# PCB.net
KiCad netlist of a schematic drawn in Altium Designer
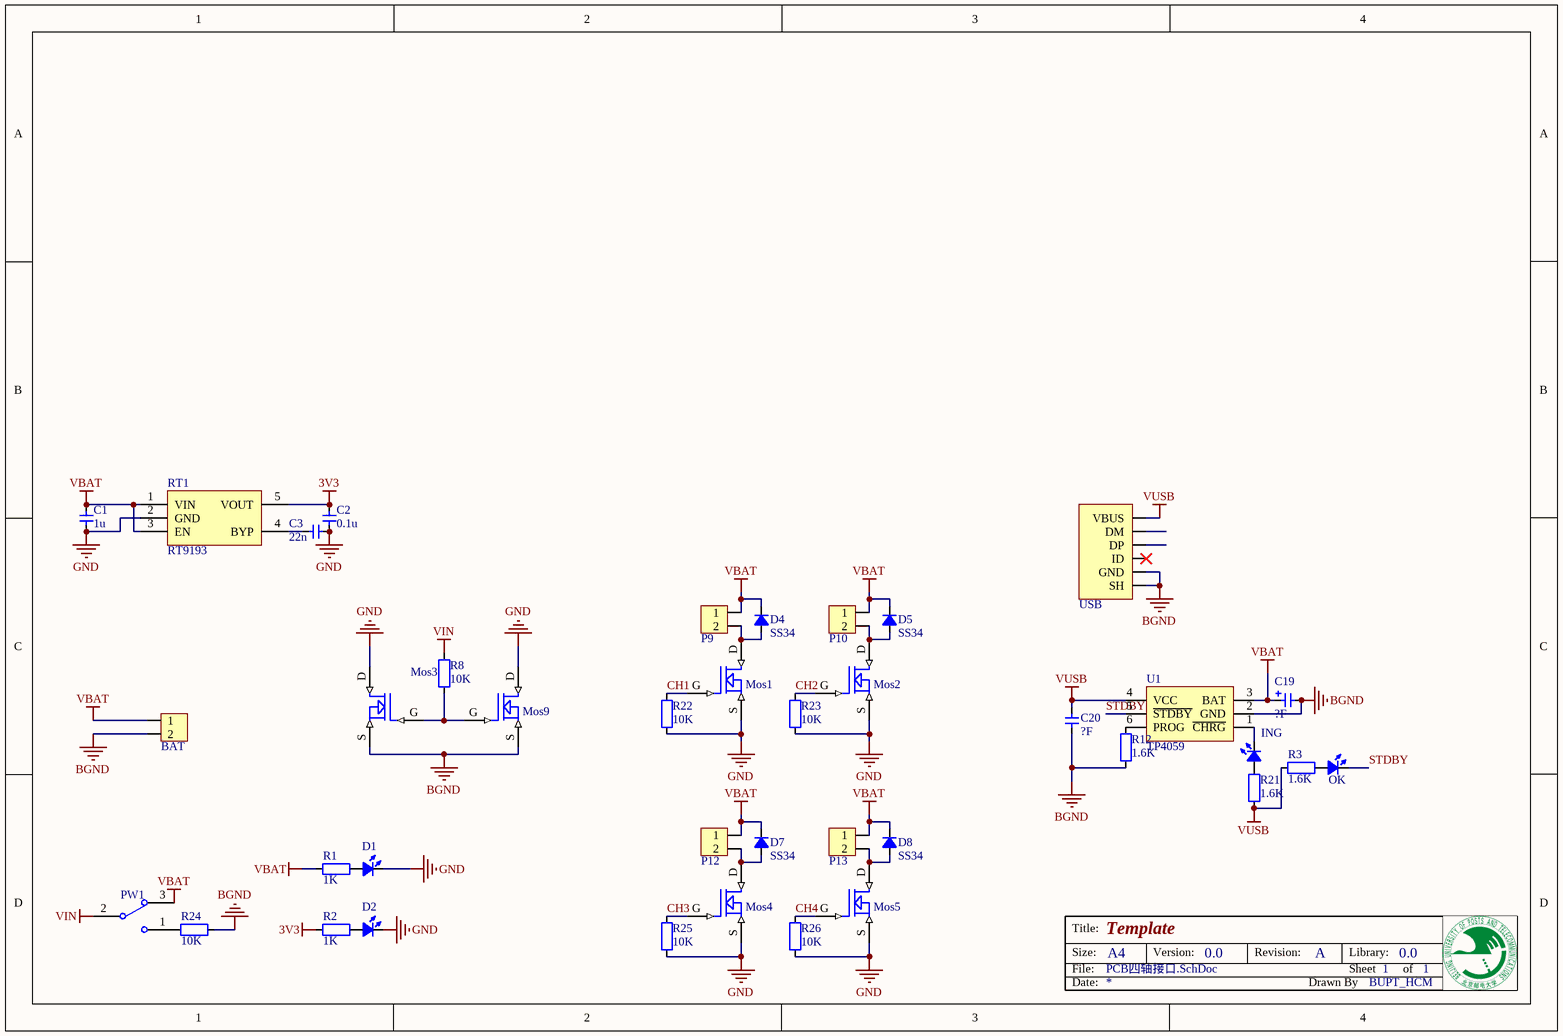
[diagram p0: PCB四轴接口.SchDoc]

(export (version "E")
  (design (tool "Eeschema 10.0.6"))
  (components
    (comp (ref "BAT")
      (value "HDR1x2_2.54")
      (footprint "PCB_ConnectorHDR:HDR1X2_2.54_90")
      (description "Header")
      (libsource (lib "SCH_ConnectorHDR") (part "HDR1x2_2.54"))
    )
    (comp (ref "C1")
      (value "1u")
      (footprint "PCB_PassiveCap:CAP_0603")
      (description "Capacitor")
      (fields (field (name "Comment") "Cap_0603"))
      (libsource (lib "SCH_Passive") (part "Cap_0603"))
    )
    (comp (ref "C2")
      (value "0.1u")
      (footprint "PCB_PassiveCap:CAP_0603")
      (description "Capacitor")
      (fields (field (name "Comment") "Cap_0603"))
      (libsource (lib "SCH_Passive") (part "Cap_0603"))
    )
    (comp (ref "C3")
      (value "22n")
      (footprint "PCB_PassiveCap:CAP_0603")
      (description "Capacitor")
      (fields (field (name "Comment") "Cap_0603"))
      (libsource (lib "SCH_Passive") (part "Cap_0603"))
    )
    (comp (ref "C19")
      (value "?F")
      (footprint "PCB_PassiveCap:CAP_TAN_D2917")
      (description "Capacitor")
      (fields (field (name "Comment") "Cap_Tan_2917"))
      (libsource (lib "SCH_Passive") (part "Cap_Tan_2917"))
    )
    (comp (ref "C20")
      (value "?F")
      (footprint "PCB_PassiveCap:CAP_0805")
      (description "Capacitor")
      (fields (field (name "Comment") "Cap_0805"))
      (libsource (lib "SCH_Passive") (part "Cap_0805"))
    )
    (comp (ref "D1")
      (value "LED_0805")
      (footprint "PCB_ActiveLED:LED_0805_YELLOW")
      (description "LED")
      (libsource (lib "SCH_Active") (part "LED_0805"))
    )
    (comp (ref "D2")
      (value "LED_0805")
      (footprint "PCB_ActiveLED:LED_0805_YELLOW")
      (description "LED")
      (libsource (lib "SCH_Active") (part "LED_0805"))
    )
    (comp (ref "D4")
      (value "SS34")
      (footprint "PCB_ActiveDIO:DO-214AC")
      (description "Diode")
      (fields (field (name "Comment") "Diode_SMA"))
      (libsource (lib "SCH_Active") (part "Diode_SMA"))
    )
    (comp (ref "D5")
      (value "SS34")
      (footprint "PCB_ActiveDIO:DO-214AC")
      (description "Diode")
      (fields (field (name "Comment") "Diode_SMA"))
      (libsource (lib "SCH_Active") (part "Diode_SMA"))
    )
    (comp (ref "D7")
      (value "SS34")
      (footprint "PCB_ActiveDIO:DO-214AC")
      (description "Diode")
      (fields (field (name "Comment") "Diode_SMA"))
      (libsource (lib "SCH_Active") (part "Diode_SMA"))
    )
    (comp (ref "D8")
      (value "SS34")
      (footprint "PCB_ActiveDIO:DO-214AC")
      (description "Diode")
      (fields (field (name "Comment") "Diode_SMA"))
      (libsource (lib "SCH_Active") (part "Diode_SMA"))
    )
    (comp (ref "ING")
      (value "LED_0805")
      (footprint "PCB_ActiveLED:LED_0805_RED")
      (description "LED")
      (libsource (lib "SCH_Active") (part "LED_0805"))
    )
    (comp (ref "Mos1")
      (value "MOSFET N")
      (footprint "Nmos_SOT23")
      (description "MOS SOT23")
      (libsource (lib "SCH_Active") (part "MOSFET N"))
    )
    (comp (ref "Mos2")
      (value "MOSFET N")
      (footprint "Nmos_SOT23")
      (description "MOS SOT23")
      (libsource (lib "SCH_Active") (part "MOSFET N"))
    )
    (comp (ref "Mos3")
      (value "MOSFET N")
      (footprint "Nmos_SOT23")
      (description "MOS SOT23")
      (libsource (lib "SCH_Active") (part "MOSFET N"))
    )
    (comp (ref "Mos4")
      (value "MOSFET N")
      (footprint "Nmos_SOT23")
      (description "MOS SOT23")
      (libsource (lib "SCH_Active") (part "MOSFET N"))
    )
    (comp (ref "Mos5")
      (value "MOSFET N")
      (footprint "Nmos_SOT23")
      (description "MOS SOT23")
      (libsource (lib "SCH_Active") (part "MOSFET N"))
    )
    (comp (ref "Mos9")
      (value "MOSFET N")
      (footprint "Nmos_SOT23")
      (description "MOS SOT23")
      (libsource (lib "SCH_Active") (part "MOSFET N"))
    )
    (comp (ref "OK")
      (value "LED_0805")
      (footprint "PCB_ActiveLED:LED_0805_GREEN")
      (description "LED")
      (libsource (lib "SCH_Active") (part "LED_0805"))
    )
    (comp (ref "P9")
      (value "HDR1x2_2.54")
      (footprint "PCB_ConnectorHDR:HDR1X2_2.54_180")
      (description "Header")
      (libsource (lib "SCH_ConnectorHDR") (part "HDR1x2_2.54T"))
    )
    (comp (ref "P10")
      (value "HDR1x2_2.54")
      (footprint "PCB_ConnectorHDR:HDR1X2_2.54_180")
      (description "Header")
      (libsource (lib "SCH_ConnectorHDR") (part "HDR1x2_2.54T"))
    )
    (comp (ref "P12")
      (value "HDR1x2_2.54")
      (footprint "PCB_ConnectorHDR:HDR1X2_2.54_180")
      (description "Header")
      (libsource (lib "SCH_ConnectorHDR") (part "HDR1x2_2.54T"))
    )
    (comp (ref "P13")
      (value "HDR1x2_2.54")
      (footprint "PCB_ConnectorHDR:HDR1X2_2.54_180")
      (description "Header")
      (libsource (lib "SCH_ConnectorHDR") (part "HDR1x2_2.54T"))
    )
    (comp (ref "PW1")
      (value "SwitchSPDT_2.8x6.6_90")
      (footprint "PCB_Switch:SwitchSPDT_2.8X6.6_90")
      (description "Switch")
      (libsource (lib "SCH_Switch") (part "SwitchSPDT_2.8x6.6_90"))
    )
    (comp (ref "R1")
      (value "1K")
      (footprint "PCB_PassiveRes:RES_0603")
      (description "Resistor")
      (fields (field (name "Comment") "Res_0603"))
      (libsource (lib "SCH_Passive") (part "Res_0603"))
    )
    (comp (ref "R2")
      (value "1K")
      (footprint "PCB_PassiveRes:RES_0603")
      (description "Resistor")
      (fields (field (name "Comment") "Res_0603"))
      (libsource (lib "SCH_Passive") (part "Res_0603"))
    )
    (comp (ref "R3")
      (value "1.6K")
      (footprint "PCB_PassiveRes:RES_0603")
      (description "Resistor")
      (fields (field (name "Comment") "Res_0603"))
      (libsource (lib "SCH_Passive") (part "Res_0603"))
    )
    (comp (ref "R8")
      (value "10K")
      (footprint "PCB_PassiveRes:RES_0603")
      (description "Resistor")
      (fields (field (name "Comment") "Res_0603"))
      (libsource (lib "") (part "Res_0603_1"))
    )
    (comp (ref "R12")
      (value "1.6K")
      (footprint "PCB_PassiveRes:RES_0603")
      (description "Resistor")
      (fields (field (name "Comment") "Res_0603"))
      (libsource (lib "") (part "Res_0603_2"))
    )
    (comp (ref "R21")
      (value "1.6K")
      (footprint "PCB_PassiveRes:RES_0603")
      (description "Resistor")
      (fields (field (name "Comment") "Res_0603"))
      (libsource (lib "") (part "Res_0603_2"))
    )
    (comp (ref "R22")
      (value "10K")
      (footprint "PCB_PassiveRes:RES_0603")
      (description "Resistor")
      (fields (field (name "Comment") "Res_0603"))
      (libsource (lib "") (part "Res_0603_1"))
    )
    (comp (ref "R23")
      (value "10K")
      (footprint "PCB_PassiveRes:RES_0603")
      (description "Resistor")
      (fields (field (name "Comment") "Res_0603"))
      (libsource (lib "") (part "Res_0603_1"))
    )
    (comp (ref "R24")
      (value "10K")
      (footprint "PCB_PassiveRes:RES_0603")
      (description "Resistor")
      (fields (field (name "Comment") "Res_0603"))
      (libsource (lib "SCH_Passive") (part "Res_0603"))
    )
    (comp (ref "R25")
      (value "10K")
      (footprint "PCB_PassiveRes:RES_0603")
      (description "Resistor")
      (fields (field (name "Comment") "Res_0603"))
      (libsource (lib "") (part "Res_0603_1"))
    )
    (comp (ref "R26")
      (value "10K")
      (footprint "PCB_PassiveRes:RES_0603")
      (description "Resistor")
      (fields (field (name "Comment") "Res_0603"))
      (libsource (lib "") (part "Res_0603_1"))
    )
    (comp (ref "RT1")
      (value "RT9193")
      (footprint "PCB_IntegratedCircuit:SOT23-5")
      (description "Power")
      (libsource (lib "SCH_IntegratedCircuit") (part "RT9193"))
    )
    (comp (ref "U1")
      (value "TP4059")
      (footprint "SOT23-6")
      (libsource (lib "SCH_IntegratedCircuit") (part "TP4059"))
    )
    (comp (ref "USB")
      (value "USB_Micro")
      (footprint "PCB_USB:USB_Micro-AB")
      (description "USB")
      (libsource (lib "SCH_USB") (part "USB_Micro"))
    )
  )
  (nets
    (net (code "1") (name "/CH1") (class "Default")
      (node (ref "Mos1") (pin "G") (pinfunction "G_G") (pintype "input"))
      (node (ref "R22") (pin "2") (pinfunction "2_2") (pintype "passive"))
    )
    (net (code "2") (name "/CH2") (class "Default")
      (node (ref "Mos2") (pin "G") (pinfunction "G_G") (pintype "input"))
      (node (ref "R23") (pin "2") (pinfunction "2_2") (pintype "passive"))
    )
    (net (code "3") (name "/CH3") (class "Default")
      (node (ref "Mos4") (pin "G") (pinfunction "G_G") (pintype "input"))
      (node (ref "R25") (pin "2") (pinfunction "2_2") (pintype "passive"))
    )
    (net (code "4") (name "/CH4") (class "Default")
      (node (ref "Mos5") (pin "G") (pinfunction "G_G") (pintype "input"))
      (node (ref "R26") (pin "2") (pinfunction "2_2") (pintype "passive"))
    )
    (net (code "5") (name "/STDBY") (class "Default")
      (node (ref "OK") (pin "2") (pinfunction "K_2") (pintype "passive"))
      (node (ref "U1") (pin "5") (pinfunction "~{STDBY}_5") (pintype "passive"))
    )
    (net (code "6") (name "3V3") (class "Default")
      (node (ref "C2") (pin "2") (pinfunction "2_2") (pintype "passive"))
      (node (ref "R2") (pin "1") (pinfunction "1_1") (pintype "passive"))
      (node (ref "RT1") (pin "5") (pinfunction "VOUT_5") (pintype "passive"))
    )
    (net (code "7") (name "BGND") (class "Default")
      (node (ref "BAT") (pin "2") (pinfunction "2_2") (pintype "passive"))
      (node (ref "C19") (pin "2") (pinfunction "2_2") (pintype "passive"))
      (node (ref "C20") (pin "1") (pinfunction "1_1") (pintype "passive"))
      (node (ref "Mos3") (pin "S") (pinfunction "S_S") (pintype "input"))
      (node (ref "Mos9") (pin "S") (pinfunction "S_S") (pintype "input"))
      (node (ref "R12") (pin "2") (pinfunction "2_2") (pintype "passive"))
      (node (ref "R24") (pin "2") (pinfunction "2_2") (pintype "passive"))
      (node (ref "U1") (pin "2") (pinfunction "GND_2") (pintype "passive"))
      (node (ref "USB") (pin "0") (pinfunction "SH_0") (pintype "passive"))
      (node (ref "USB") (pin "5") (pinfunction "GND_5") (pintype "passive"))
    )
    (net (code "8") (name "GND") (class "Default")
      (node (ref "C1") (pin "1") (pinfunction "1_1") (pintype "passive"))
      (node (ref "C2") (pin "1") (pinfunction "1_1") (pintype "passive"))
      (node (ref "C3") (pin "1") (pinfunction "1_1") (pintype "passive"))
      (node (ref "D1") (pin "2") (pinfunction "K_2") (pintype "passive"))
      (node (ref "D2") (pin "2") (pinfunction "K_2") (pintype "passive"))
      (node (ref "Mos1") (pin "S") (pinfunction "S_S") (pintype "input"))
      (node (ref "Mos2") (pin "S") (pinfunction "S_S") (pintype "input"))
      (node (ref "Mos3") (pin "D") (pinfunction "D_D") (pintype "input"))
      (node (ref "Mos4") (pin "S") (pinfunction "S_S") (pintype "input"))
      (node (ref "Mos5") (pin "S") (pinfunction "S_S") (pintype "input"))
      (node (ref "Mos9") (pin "D") (pinfunction "D_D") (pintype "input"))
      (node (ref "R22") (pin "1") (pinfunction "1_1") (pintype "passive"))
      (node (ref "R23") (pin "1") (pinfunction "1_1") (pintype "passive"))
      (node (ref "R25") (pin "1") (pinfunction "1_1") (pintype "passive"))
      (node (ref "R26") (pin "1") (pinfunction "1_1") (pintype "passive"))
      (node (ref "RT1") (pin "2") (pinfunction "GND_2") (pintype "passive"))
    )
    (net (code "9") (name "Net-(D1-A)") (class "Default")
      (node (ref "D1") (pin "1") (pinfunction "A_1") (pintype "passive"))
      (node (ref "R1") (pin "2") (pinfunction "2_2") (pintype "passive"))
    )
    (net (code "10") (name "Net-(D2-A)") (class "Default")
      (node (ref "D2") (pin "1") (pinfunction "A_1") (pintype "passive"))
      (node (ref "R2") (pin "2") (pinfunction "2_2") (pintype "passive"))
    )
    (net (code "11") (name "Net-(D4-A)") (class "Default")
      (node (ref "D4") (pin "1") (pinfunction "A_1") (pintype "passive"))
      (node (ref "Mos1") (pin "D") (pinfunction "D_D") (pintype "input"))
      (node (ref "P9") (pin "2") (pinfunction "2_2") (pintype "passive"))
    )
    (net (code "12") (name "Net-(D5-A)") (class "Default")
      (node (ref "D5") (pin "1") (pinfunction "A_1") (pintype "passive"))
      (node (ref "Mos2") (pin "D") (pinfunction "D_D") (pintype "input"))
      (node (ref "P10") (pin "2") (pinfunction "2_2") (pintype "passive"))
    )
    (net (code "13") (name "Net-(D7-A)") (class "Default")
      (node (ref "D7") (pin "1") (pinfunction "A_1") (pintype "passive"))
      (node (ref "Mos4") (pin "D") (pinfunction "D_D") (pintype "input"))
      (node (ref "P12") (pin "2") (pinfunction "2_2") (pintype "passive"))
    )
    (net (code "14") (name "Net-(D8-A)") (class "Default")
      (node (ref "D8") (pin "1") (pinfunction "A_1") (pintype "passive"))
      (node (ref "Mos5") (pin "D") (pinfunction "D_D") (pintype "input"))
      (node (ref "P13") (pin "2") (pinfunction "2_2") (pintype "passive"))
    )
    (net (code "15") (name "Net-(ING-A)") (class "Default")
      (node (ref "ING") (pin "1") (pinfunction "A_1") (pintype "passive"))
      (node (ref "R21") (pin "1") (pinfunction "1_1") (pintype "passive"))
    )
    (net (code "16") (name "Net-(ING-K)") (class "Default")
      (node (ref "ING") (pin "2") (pinfunction "K_2") (pintype "passive"))
      (node (ref "U1") (pin "1") (pinfunction "~{CHRG}_1") (pintype "passive"))
    )
    (net (code "17") (name "Net-(Mos3-PadG)") (class "Default")
      (node (ref "Mos3") (pin "G") (pinfunction "G_G") (pintype "input"))
      (node (ref "Mos9") (pin "G") (pinfunction "G_G") (pintype "input"))
      (node (ref "R8") (pin "1") (pinfunction "1_1") (pintype "passive"))
    )
    (net (code "18") (name "Net-(OK-A)") (class "Default")
      (node (ref "OK") (pin "1") (pinfunction "A_1") (pintype "passive"))
      (node (ref "R3") (pin "2") (pinfunction "2_2") (pintype "passive"))
    )
    (net (code "19") (name "Net-(PW1-Pad1)") (class "Default")
      (node (ref "PW1") (pin "1") (pinfunction "1_1") (pintype "passive"))
      (node (ref "R24") (pin "1") (pinfunction "1_1") (pintype "passive"))
    )
    (net (code "20") (name "Net-(RT1-BYP)") (class "Default")
      (node (ref "C3") (pin "2") (pinfunction "2_2") (pintype "passive"))
      (node (ref "RT1") (pin "4") (pinfunction "BYP_4") (pintype "passive"))
    )
    (net (code "21") (name "Net-(U1-PROG)") (class "Default")
      (node (ref "R12") (pin "1") (pinfunction "1_1") (pintype "passive"))
      (node (ref "U1") (pin "6") (pinfunction "PROG_6") (pintype "passive"))
    )
    (net (code "22") (name "VBAT") (class "Default")
      (node (ref "BAT") (pin "1") (pinfunction "1_1") (pintype "passive"))
      (node (ref "C1") (pin "2") (pinfunction "2_2") (pintype "passive"))
      (node (ref "C19") (pin "1") (pinfunction "1_1") (pintype "passive"))
      (node (ref "D4") (pin "2") (pinfunction "K_2") (pintype "passive"))
      (node (ref "D5") (pin "2") (pinfunction "K_2") (pintype "passive"))
      (node (ref "D7") (pin "2") (pinfunction "K_2") (pintype "passive"))
      (node (ref "D8") (pin "2") (pinfunction "K_2") (pintype "passive"))
      (node (ref "P10") (pin "1") (pinfunction "1_1") (pintype "passive"))
      (node (ref "P12") (pin "1") (pinfunction "1_1") (pintype "passive"))
      (node (ref "P13") (pin "1") (pinfunction "1_1") (pintype "passive"))
      (node (ref "P9") (pin "1") (pinfunction "1_1") (pintype "passive"))
      (node (ref "PW1") (pin "3") (pinfunction "3_3") (pintype "passive"))
      (node (ref "R1") (pin "1") (pinfunction "1_1") (pintype "passive"))
      (node (ref "RT1") (pin "1") (pinfunction "VIN_1") (pintype "passive"))
      (node (ref "RT1") (pin "3") (pinfunction "EN_3") (pintype "power_in"))
      (node (ref "U1") (pin "3") (pinfunction "BAT_3") (pintype "passive"))
    )
    (net (code "23") (name "VIN") (class "Default")
      (node (ref "PW1") (pin "2") (pinfunction "2_2") (pintype "passive"))
      (node (ref "R8") (pin "2") (pinfunction "2_2") (pintype "passive"))
    )
    (net (code "24") (name "VUSB") (class "Default")
      (node (ref "C20") (pin "2") (pinfunction "2_2") (pintype "passive"))
      (node (ref "R21") (pin "2") (pinfunction "2_2") (pintype "passive"))
      (node (ref "R3") (pin "1") (pinfunction "1_1") (pintype "passive"))
      (node (ref "U1") (pin "4") (pinfunction "VCC_4") (pintype "passive"))
      (node (ref "USB") (pin "1") (pinfunction "VBUS_1") (pintype "passive"))
    )
    (net (code "25") (name "unconnected-(USB-DM-Pad2)") (class "Default")
      (node (ref "USB") (pin "2") (pinfunction "DM_2") (pintype "passive"))
    )
    (net (code "26") (name "unconnected-(USB-DP-Pad3)") (class "Default")
      (node (ref "USB") (pin "3") (pinfunction "DP_3") (pintype "passive"))
    )
    (net (code "27") (name "unconnected-(USB-ID-Pad4)") (class "Default")
      (node (ref "USB") (pin "4") (pinfunction "ID_4") (pintype "passive+no_connect"))
    )
  )
)
